# BH1750_V1_0.net
KiCad netlist of a schematic drawn in EAGLE
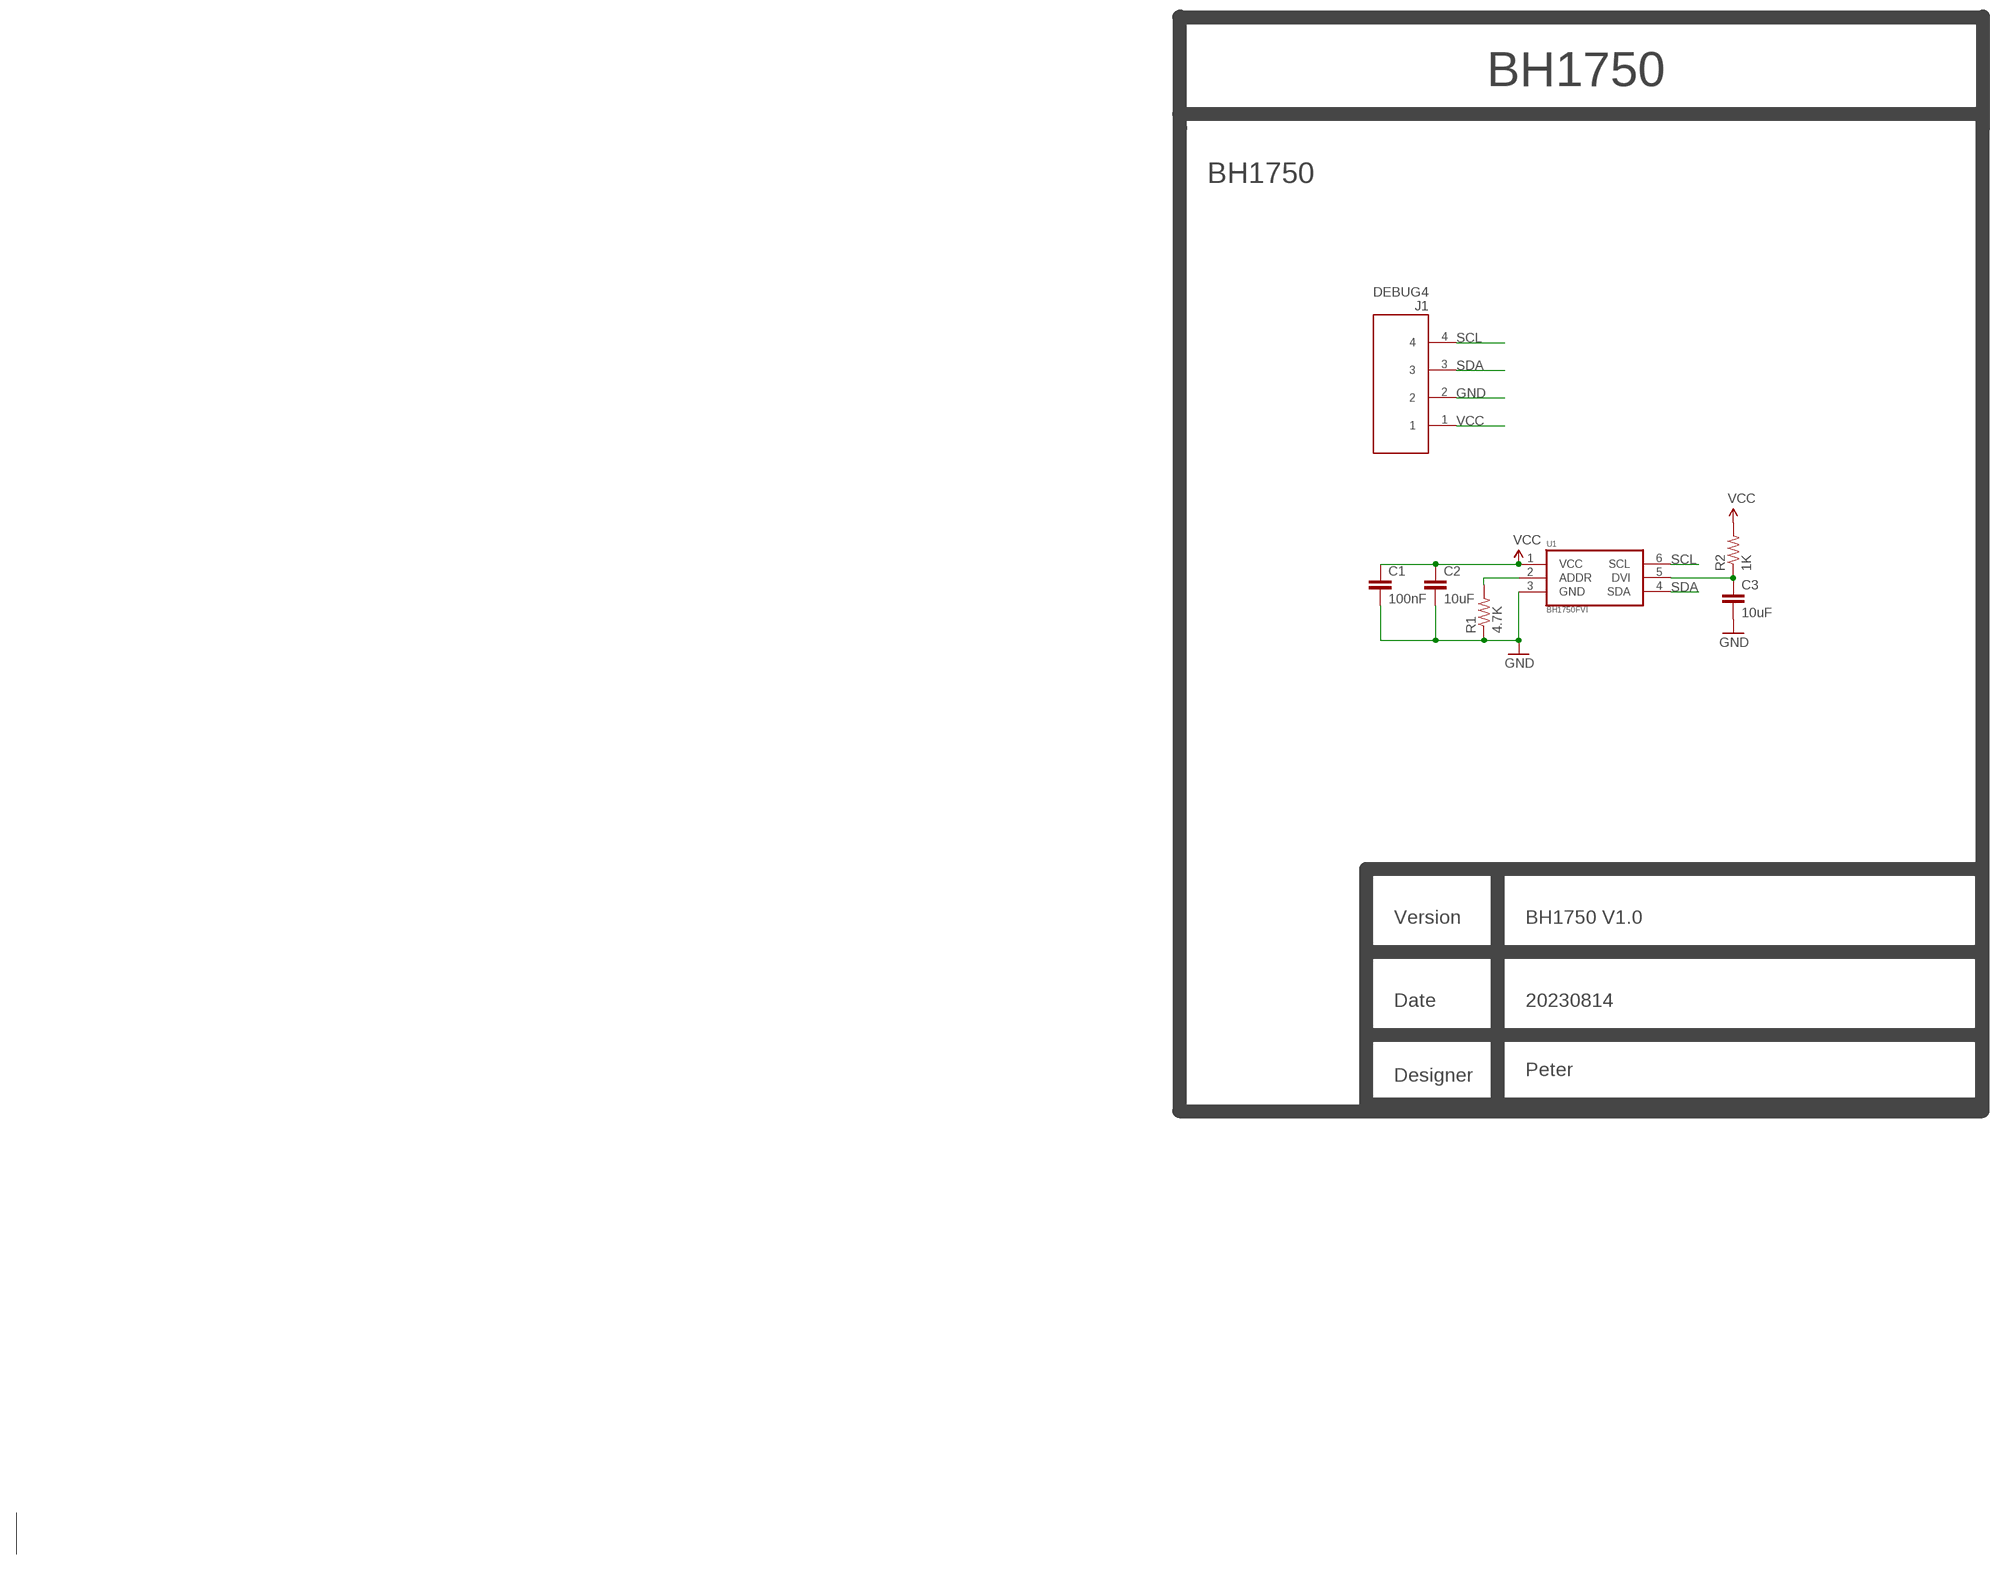
[diagram p0: schematic, sheet 1]

(export (version "E")
  (design (tool "Eeschema 10.0.6"))
  (components
    (comp (ref "C1")
      (value "100nF")
      (footprint "eagle-import:C0603")
      (libsource (lib "eagle-import") (part "C0603"))
    )
    (comp (ref "C2")
      (value "10uF")
      (footprint "eagle-import:C0603")
      (libsource (lib "eagle-import") (part "C0603"))
    )
    (comp (ref "C3")
      (value "10uF")
      (footprint "eagle-import:C0603")
      (libsource (lib "eagle-import") (part "C0603"))
    )
    (comp (ref "J1")
      (value "DEBUG4")
      (footprint "eagle-import:DEBUG_4")
      (libsource (lib "eagle-import") (part "DEBUG4"))
    )
    (comp (ref "R1")
      (value "4.7K")
      (footprint "eagle-import:R0603")
      (libsource (lib "eagle-import") (part "R0603"))
    )
    (comp (ref "R2")
      (value "1K")
      (footprint "eagle-import:R0603")
      (libsource (lib "eagle-import") (part "R0603"))
    )
    (comp (ref "U1")
      (value "BH1750FVI")
      (footprint "eagle-import:WSOF6I")
      (libsource (lib "eagle-import") (part "BH1750FVI"))
    )
  )
  (nets
    (net (code "1") (name "/SCL") (class "Default")
      (node (ref "J1") (pin "4") (pinfunction "4_4") (pintype "bidirectional"))
      (node (ref "U1") (pin "6") (pinfunction "SCL_6") (pintype "bidirectional"))
    )
    (net (code "2") (name "/SDA") (class "Default")
      (node (ref "J1") (pin "3") (pinfunction "3_3") (pintype "bidirectional"))
      (node (ref "U1") (pin "4") (pinfunction "SDA_4") (pintype "bidirectional"))
    )
    (net (code "3") (name "GND") (class "Default")
      (node (ref "C1") (pin "2") (pinfunction "2_2") (pintype "passive"))
      (node (ref "C2") (pin "2") (pinfunction "2_2") (pintype "passive"))
      (node (ref "C3") (pin "2") (pinfunction "2_2") (pintype "passive"))
      (node (ref "J1") (pin "2") (pinfunction "2_2") (pintype "bidirectional"))
      (node (ref "R1") (pin "1") (pinfunction "1_1") (pintype "passive"))
      (node (ref "U1") (pin "3") (pinfunction "GND_3") (pintype "bidirectional"))
    )
    (net (code "4") (name "Net-(U1-ADDR)") (class "Default")
      (node (ref "R1") (pin "2") (pinfunction "2_2") (pintype "passive"))
      (node (ref "U1") (pin "2") (pinfunction "ADDR_2") (pintype "bidirectional"))
    )
    (net (code "5") (name "Net-(U1-DVI)") (class "Default")
      (node (ref "C3") (pin "1") (pinfunction "1_1") (pintype "passive"))
      (node (ref "R2") (pin "1") (pinfunction "1_1") (pintype "passive"))
      (node (ref "U1") (pin "5") (pinfunction "DVI_5") (pintype "bidirectional"))
    )
    (net (code "6") (name "VCC") (class "Default")
      (node (ref "C1") (pin "1") (pinfunction "1_1") (pintype "passive"))
      (node (ref "C2") (pin "1") (pinfunction "1_1") (pintype "passive"))
      (node (ref "J1") (pin "1") (pinfunction "1_1") (pintype "bidirectional"))
      (node (ref "R2") (pin "2") (pinfunction "2_2") (pintype "passive"))
      (node (ref "U1") (pin "1") (pinfunction "VCC_1") (pintype "bidirectional"))
    )
  )
)
